# Button-Board.net
KiCad netlist of a schematic drawn in EAGLE
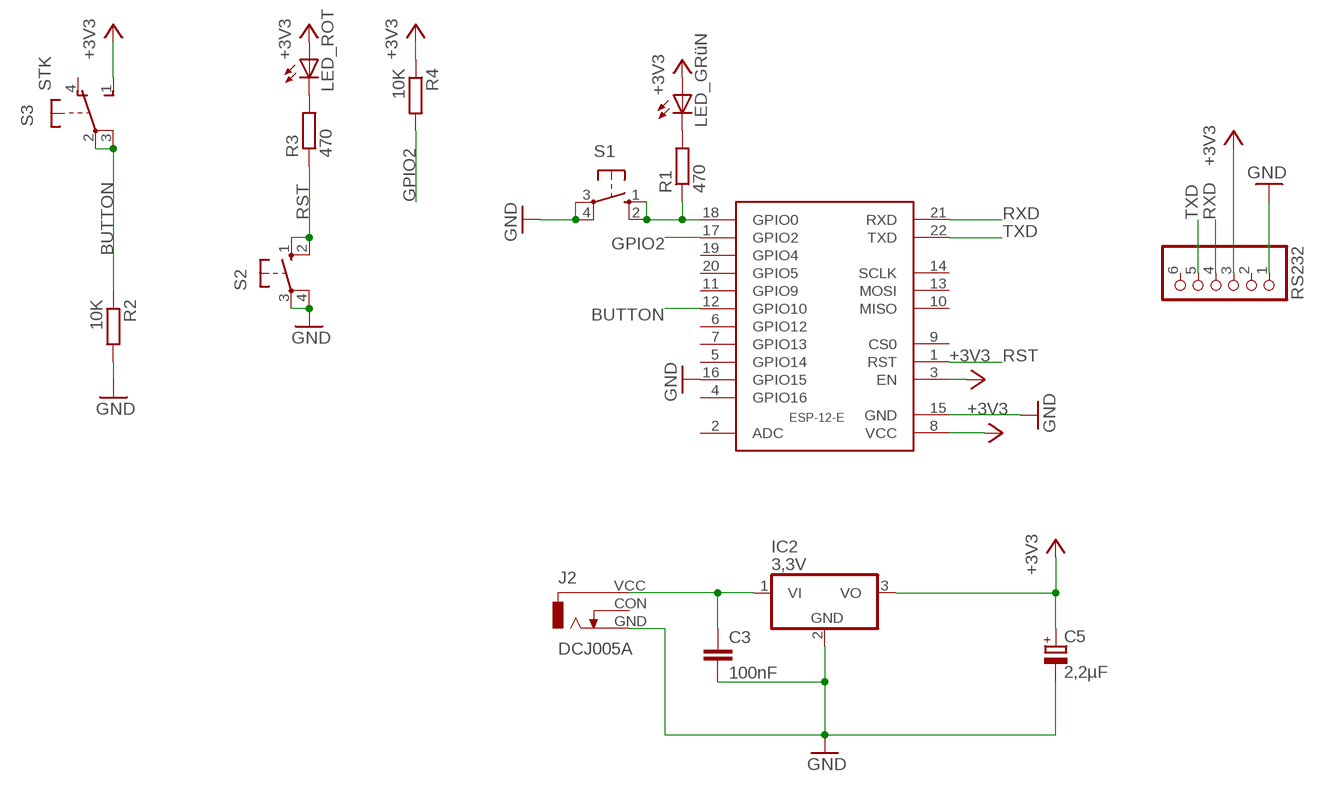
[diagram p0: schematic, sheet 1]

(export (version "E")
  (design (tool "Eeschema 10.0.6"))
  (components
    (comp (ref "C3")
      (value "100nF")
      (footprint "eagle-import:C050-030X075")
      (libsource (lib "eagle-import") (part "C-EU050-030X075"))
    )
    (comp (ref "C5")
      (value "2,2µF")
      (footprint "eagle-import:E2,5-6")
      (libsource (lib "eagle-import") (part "CPOL-EUE2.5-6"))
    )
    (comp (ref "IC2")
      (value "3,3V")
      (footprint "eagle-import:TO220V")
      (libsource (lib "eagle-import") (part "78TV05"))
    )
    (comp (ref "J2")
      (value "DCJ005A")
      (footprint "eagle-import:DC005A")
      (libsource (lib "eagle-import") (part "DCJ005A"))
    )
    (comp (ref "LED_GRüN")
      (value "LED5MM")
      (footprint "eagle-import:LED5MM")
      (libsource (lib "eagle-import") (part "LED5MM"))
    )
    (comp (ref "LED_ROT")
      (value "LED5MM")
      (footprint "eagle-import:LED5MM")
      (libsource (lib "eagle-import") (part "LED5MM"))
    )
    (comp (ref "R1")
      (value "470")
      (footprint "eagle-import:0207_10")
      (libsource (lib "eagle-import") (part "R-EU_0207/10"))
    )
    (comp (ref "R2")
      (value "10K")
      (footprint "eagle-import:0207_10")
      (libsource (lib "eagle-import") (part "R-EU_0207/10"))
    )
    (comp (ref "R3")
      (value "470")
      (footprint "eagle-import:0207_10")
      (libsource (lib "eagle-import") (part "R-EU_0207/10"))
    )
    (comp (ref "R4")
      (value "10K")
      (footprint "eagle-import:0207_10")
      (libsource (lib "eagle-import") (part "R-EU_0207/10"))
    )
    (comp (ref "RS232")
      (value "PINHD-1X6")
      (footprint "eagle-import:1X06")
      (libsource (lib "eagle-import") (part "PINHD-1X6"))
    )
    (comp (ref "S1")
      (value "10-XX")
      (footprint "eagle-import:B3F-10XX")
      (fields (field (name "MPN") "B3F-1000"))
      (libsource (lib "eagle-import") (part "10-XX"))
    )
    (comp (ref "S2")
      (value "10-XX")
      (footprint "eagle-import:B3F-10XX")
      (fields (field (name "MPN") "B3F-1000"))
      (libsource (lib "eagle-import") (part "10-XX"))
    )
    (comp (ref "S3")
      (value "STK")
      (footprint "eagle-import:STK")
      (libsource (lib "eagle-import") (part "STK"))
    )
    (comp (ref "U$1")
      (value "ESP-12-E")
      (footprint "eagle-import:ESP-12-E")
      (libsource (lib "eagle-import") (part "ESP-12-E"))
    )
  )
  (nets
    (net (code "1") (name "+3V3") (class "Default")
      (node (ref "C5") (pin "+") (pinfunction "+_+") (pintype "passive"))
      (node (ref "IC2") (pin "3") (pinfunction "VO_3") (pintype "passive"))
      (node (ref "LED_GRüN") (pin "A") (pinfunction "A_A") (pintype "passive"))
      (node (ref "LED_ROT") (pin "A") (pinfunction "A_A") (pintype "passive"))
      (node (ref "R4") (pin "1") (pinfunction "1_1") (pintype "passive"))
      (node (ref "RS232") (pin "3") (pinfunction "3_3") (pintype "passive"))
      (node (ref "S3") (pin "1") (pinfunction "S_1") (pintype "passive"))
      (node (ref "U$1") (pin "3") (pinfunction "EN_3") (pintype "bidirectional"))
      (node (ref "U$1") (pin "8") (pinfunction "VCC_8") (pintype "power_in"))
    )
    (net (code "2") (name "/BUTTON") (class "Default")
      (node (ref "R2") (pin "1") (pinfunction "1_1") (pintype "passive"))
      (node (ref "S3") (pin "2") (pinfunction "P_2") (pintype "passive"))
      (node (ref "S3") (pin "3") (pinfunction "P_3") (pintype "passive"))
      (node (ref "U$1") (pin "12") (pinfunction "GPIO10_12") (pintype "bidirectional"))
    )
    (net (code "3") (name "/GPIO2") (class "Default")
      (node (ref "R4") (pin "2") (pinfunction "2_2") (pintype "passive"))
      (node (ref "U$1") (pin "17") (pinfunction "GPIO2_17") (pintype "bidirectional"))
    )
    (net (code "4") (name "/RST") (class "Default")
      (node (ref "R3") (pin "1") (pinfunction "1_1") (pintype "passive"))
      (node (ref "S2") (pin "1") (pinfunction "S_1") (pintype "passive"))
      (node (ref "S2") (pin "2") (pinfunction "S1_2") (pintype "passive"))
      (node (ref "U$1") (pin "1") (pinfunction "RST_1") (pintype "bidirectional"))
    )
    (net (code "5") (name "/RXD") (class "Default")
      (node (ref "RS232") (pin "4") (pinfunction "4_4") (pintype "passive"))
      (node (ref "U$1") (pin "21") (pinfunction "RXD_21") (pintype "bidirectional"))
    )
    (net (code "6") (name "/TXD") (class "Default")
      (node (ref "RS232") (pin "5") (pinfunction "5_5") (pintype "passive"))
      (node (ref "U$1") (pin "22") (pinfunction "TXD_22") (pintype "bidirectional"))
    )
    (net (code "7") (name "GND") (class "Default")
      (node (ref "C3") (pin "2") (pinfunction "2_2") (pintype "passive"))
      (node (ref "C5") (pin "-") (pinfunction "-_-") (pintype "passive"))
      (node (ref "IC2") (pin "2") (pinfunction "GND_2") (pintype "passive"))
      (node (ref "J2") (pin "GND") (pinfunction "3_GND") (pintype "passive"))
      (node (ref "R2") (pin "2") (pinfunction "2_2") (pintype "passive"))
      (node (ref "RS232") (pin "1") (pinfunction "1_1") (pintype "passive"))
      (node (ref "S1") (pin "3") (pinfunction "P_3") (pintype "passive"))
      (node (ref "S1") (pin "4") (pinfunction "P1_4") (pintype "passive"))
      (node (ref "S2") (pin "3") (pinfunction "P_3") (pintype "passive"))
      (node (ref "S2") (pin "4") (pinfunction "P1_4") (pintype "passive"))
      (node (ref "U$1") (pin "15") (pinfunction "GND_15") (pintype "power_in"))
      (node (ref "U$1") (pin "16") (pinfunction "GPIO15_16") (pintype "bidirectional"))
    )
    (net (code "8") (name "Net-(IC2-VI)") (class "Default")
      (node (ref "C3") (pin "1") (pinfunction "1_1") (pintype "passive"))
      (node (ref "IC2") (pin "1") (pinfunction "VI_1") (pintype "input"))
      (node (ref "J2") (pin "VCC") (pinfunction "1_VCC") (pintype "passive"))
    )
    (net (code "9") (name "Net-(LED_GRüN-C)") (class "Default")
      (node (ref "LED_GRüN") (pin "K") (pinfunction "C_K") (pintype "passive"))
      (node (ref "R1") (pin "2") (pinfunction "2_2") (pintype "passive"))
    )
    (net (code "10") (name "Net-(LED_ROT-C)") (class "Default")
      (node (ref "LED_ROT") (pin "K") (pinfunction "C_K") (pintype "passive"))
      (node (ref "R3") (pin "2") (pinfunction "2_2") (pintype "passive"))
    )
    (net (code "11") (name "Net-(S1-S)") (class "Default")
      (node (ref "R1") (pin "1") (pinfunction "1_1") (pintype "passive"))
      (node (ref "S1") (pin "1") (pinfunction "S_1") (pintype "passive"))
      (node (ref "S1") (pin "2") (pinfunction "S1_2") (pintype "passive"))
      (node (ref "U$1") (pin "18") (pinfunction "GPIO0_18") (pintype "bidirectional"))
    )
    (net (code "12") (name "unconnected-(J2-2-PadCON)") (class "Default")
      (node (ref "J2") (pin "CON") (pinfunction "2_CON") (pintype "passive"))
    )
    (net (code "13") (name "unconnected-(RS232-Pad2)") (class "Default")
      (node (ref "RS232") (pin "2") (pinfunction "2_2") (pintype "passive"))
    )
    (net (code "14") (name "unconnected-(RS232-Pad6)") (class "Default")
      (node (ref "RS232") (pin "6") (pinfunction "6_6") (pintype "passive"))
    )
    (net (code "15") (name "unconnected-(S3-O-Pad4)") (class "Default")
      (node (ref "S3") (pin "4") (pinfunction "O_4") (pintype "passive"))
    )
    (net (code "16") (name "unconnected-(U$1-ADC-Pad2)") (class "Default")
      (node (ref "U$1") (pin "2") (pinfunction "ADC_2") (pintype "bidirectional"))
    )
    (net (code "17") (name "unconnected-(U$1-CS0-Pad9)") (class "Default")
      (node (ref "U$1") (pin "9") (pinfunction "CS0_9") (pintype "bidirectional"))
    )
    (net (code "18") (name "unconnected-(U$1-GPIO4-Pad19)") (class "Default")
      (node (ref "U$1") (pin "19") (pinfunction "GPIO4_19") (pintype "bidirectional"))
    )
    (net (code "19") (name "unconnected-(U$1-GPIO5-Pad20)") (class "Default")
      (node (ref "U$1") (pin "20") (pinfunction "GPIO5_20") (pintype "bidirectional"))
    )
    (net (code "20") (name "unconnected-(U$1-GPIO9-Pad11)") (class "Default")
      (node (ref "U$1") (pin "11") (pinfunction "GPIO9_11") (pintype "bidirectional"))
    )
    (net (code "21") (name "unconnected-(U$1-GPIO12-Pad6)") (class "Default")
      (node (ref "U$1") (pin "6") (pinfunction "GPIO12_6") (pintype "bidirectional"))
    )
    (net (code "22") (name "unconnected-(U$1-GPIO13-Pad7)") (class "Default")
      (node (ref "U$1") (pin "7") (pinfunction "GPIO13_7") (pintype "bidirectional"))
    )
    (net (code "23") (name "unconnected-(U$1-GPIO14-Pad5)") (class "Default")
      (node (ref "U$1") (pin "5") (pinfunction "GPIO14_5") (pintype "bidirectional"))
    )
    (net (code "24") (name "unconnected-(U$1-GPIO16-Pad4)") (class "Default")
      (node (ref "U$1") (pin "4") (pinfunction "GPIO16_4") (pintype "bidirectional"))
    )
    (net (code "25") (name "unconnected-(U$1-MISO-Pad10)") (class "Default")
      (node (ref "U$1") (pin "10") (pinfunction "MISO_10") (pintype "bidirectional"))
    )
    (net (code "26") (name "unconnected-(U$1-MOSI-Pad13)") (class "Default")
      (node (ref "U$1") (pin "13") (pinfunction "MOSI_13") (pintype "bidirectional"))
    )
    (net (code "27") (name "unconnected-(U$1-SCLK-Pad14)") (class "Default")
      (node (ref "U$1") (pin "14") (pinfunction "SCLK_14") (pintype "bidirectional"))
    )
  )
)
